# untitled.net
KiCad netlist of a schematic drawn in EAGLE
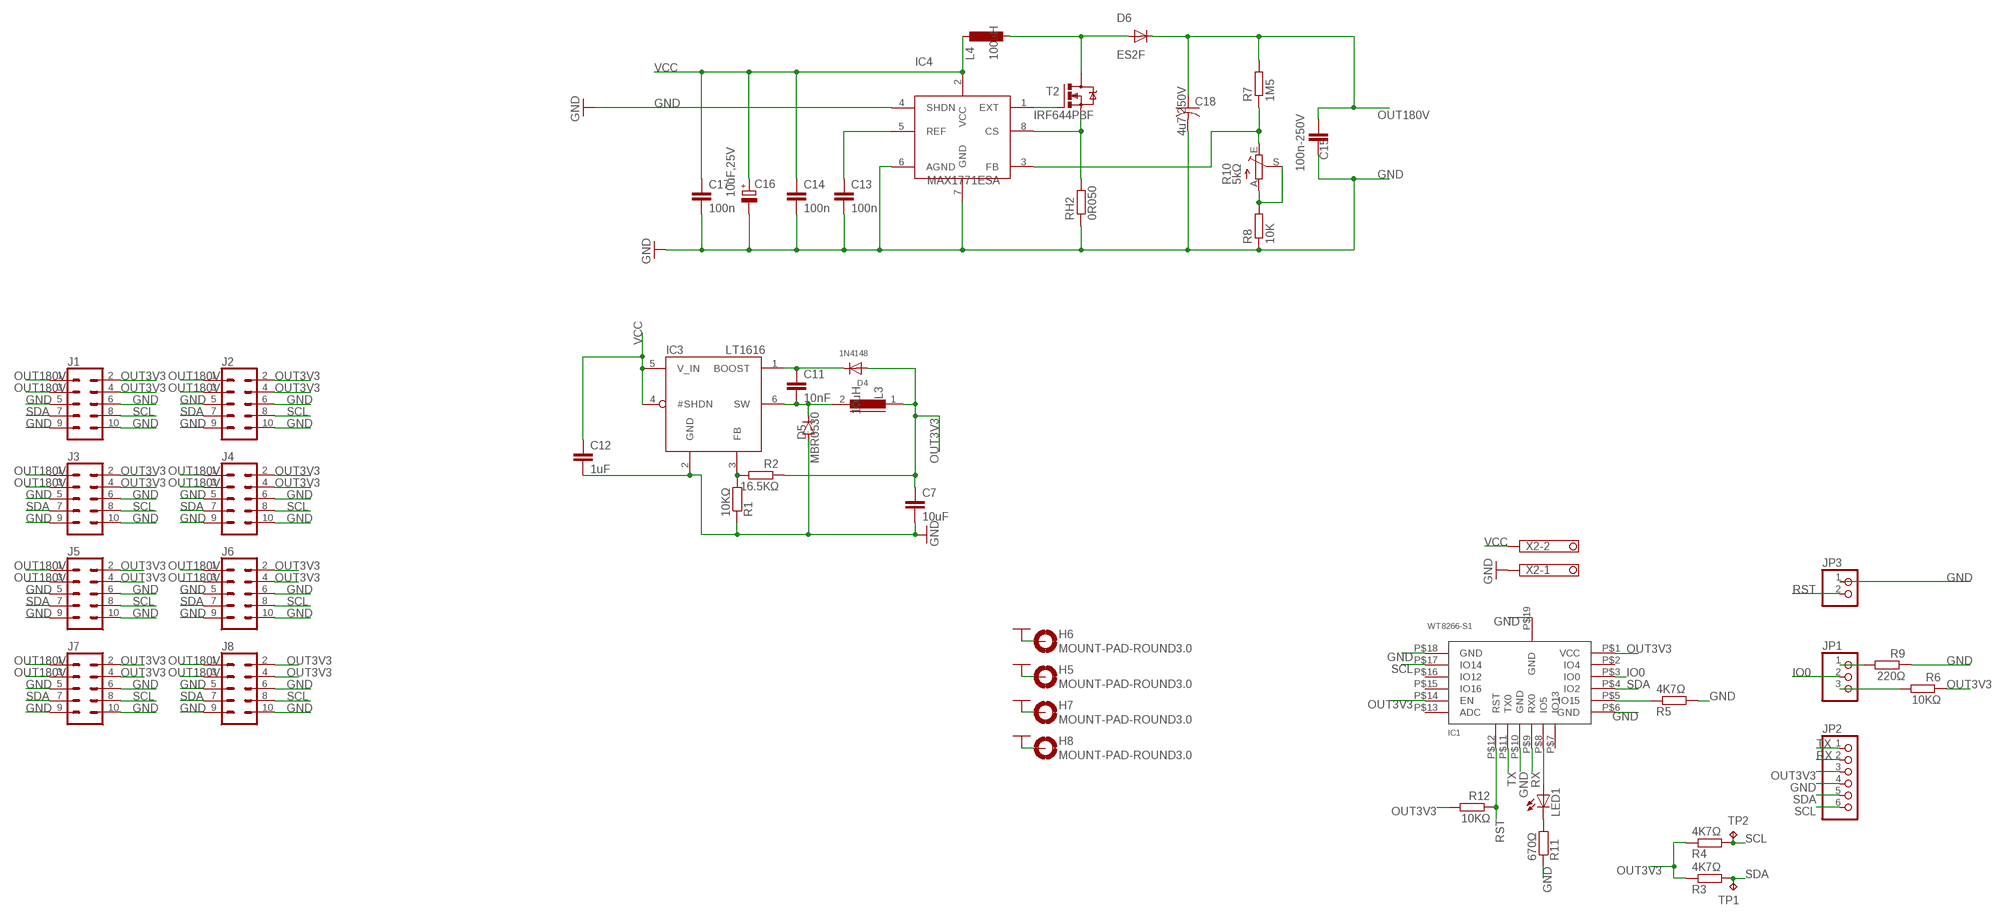
[diagram p0: schematic, sheet 1]

(export (version "E")
  (design (tool "Eeschema 10.0.6"))
  (components
    (comp (ref "C7")
      (value "10uF")
      (footprint "eagle-import:C1206")
      (libsource (lib "eagle-import") (part "C-EUC1206"))
    )
    (comp (ref "C11")
      (value "10nF")
      (footprint "eagle-import:C1206")
      (libsource (lib "eagle-import") (part "C-EUC1206"))
    )
    (comp (ref "C12")
      (value "1uF")
      (footprint "eagle-import:C1206")
      (libsource (lib "eagle-import") (part "C-EUC1206"))
    )
    (comp (ref "C13")
      (value "100n")
      (footprint "eagle-import:C1206")
      (libsource (lib "eagle-import") (part "C-EUC1206"))
    )
    (comp (ref "C14")
      (value "100n")
      (footprint "eagle-import:C1206")
      (libsource (lib "eagle-import") (part "C-EUC1206"))
    )
    (comp (ref "C15")
      (value "100n-250V")
      (footprint "eagle-import:C2420")
      (libsource (lib "eagle-import") (part "C-EU-2420"))
    )
    (comp (ref "C16")
      (value "10uF,25V")
      (footprint "eagle-import:C-EIA-7343")
      (libsource (lib "eagle-import") (part "C-POL-EU7343"))
    )
    (comp (ref "C17")
      (value "100n")
      (footprint "eagle-import:C1206")
      (libsource (lib "eagle-import") (part "C-EUC1206"))
    )
    (comp (ref "C18")
      (value "4u7 250V")
      (footprint "eagle-import:CAP_RADIAL_5MM")
      (fields
        (field (name "DIGIKEY_PART_NUMBER") "P5156-ND")
        (field (name "MANUFACTURER") "Panasonic Electronic Components")
        (field (name "MPN") "ECA-1EM102")
        (field (name "CREATED_BY") "PCBLayout.com")
      )
      (libsource (lib "eagle-import") (part "ECA-1EM102"))
    )
    (comp (ref "D4")
      (value "1N4148")
      (footprint "eagle-import:DO-1N4148")
      (libsource (lib "eagle-import") (part "DIODEDO-1N4148"))
    )
    (comp (ref "D5")
      (value "MBR0530")
      (footprint "eagle-import:SOD123")
      (libsource (lib "eagle-import") (part "diode_210_DIODE-SOD123"))
    )
    (comp (ref "D6")
      (value "ES2F")
      (footprint "eagle-import:SMC")
      (libsource (lib "eagle-import") (part "DIODE-SMC"))
    )
    (comp (ref "H5")
      (value "MOUNT-PAD-ROUND3.0")
      (footprint "eagle-import:3,0-PAD")
      (libsource (lib "eagle-import") (part "MOUNT-PAD-ROUND3.0"))
    )
    (comp (ref "H6")
      (value "MOUNT-PAD-ROUND3.0")
      (footprint "eagle-import:3,0-PAD")
      (libsource (lib "eagle-import") (part "MOUNT-PAD-ROUND3.0"))
    )
    (comp (ref "H7")
      (value "MOUNT-PAD-ROUND3.0")
      (footprint "eagle-import:3,0-PAD")
      (libsource (lib "eagle-import") (part "MOUNT-PAD-ROUND3.0"))
    )
    (comp (ref "H8")
      (value "MOUNT-PAD-ROUND3.0")
      (footprint "eagle-import:3,0-PAD")
      (libsource (lib "eagle-import") (part "MOUNT-PAD-ROUND3.0"))
    )
    (comp (ref "IC1")
      (value "WT8266-S1")
      (footprint "eagle-import:WT8266-S1")
      (libsource (lib "eagle-import") (part "WT8266-S1"))
    )
    (comp (ref "IC3")
      (value "LT1616")
      (footprint "eagle-import:SOT23-6")
      (libsource (lib "eagle-import") (part "LT1616"))
    )
    (comp (ref "IC4")
      (value "MAX1771ESA")
      (footprint "eagle-import:SO-8")
      (libsource (lib "eagle-import") (part "MAX1771ESA"))
    )
    (comp (ref "J1")
      (value "CONN_05X2PTH")
      (footprint "eagle-import:2X5")
      (libsource (lib "eagle-import") (part "CONN_05X2PTH"))
    )
    (comp (ref "J2")
      (value "CONN_05X2PTH")
      (footprint "eagle-import:2X5")
      (libsource (lib "eagle-import") (part "CONN_05X2PTH"))
    )
    (comp (ref "J3")
      (value "CONN_05X2PTH")
      (footprint "eagle-import:2X5")
      (libsource (lib "eagle-import") (part "CONN_05X2PTH"))
    )
    (comp (ref "J4")
      (value "CONN_05X2PTH")
      (footprint "eagle-import:2X5")
      (libsource (lib "eagle-import") (part "CONN_05X2PTH"))
    )
    (comp (ref "J5")
      (value "CONN_05X2PTH")
      (footprint "eagle-import:2X5")
      (libsource (lib "eagle-import") (part "CONN_05X2PTH"))
    )
    (comp (ref "J6")
      (value "CONN_05X2PTH")
      (footprint "eagle-import:2X5")
      (libsource (lib "eagle-import") (part "CONN_05X2PTH"))
    )
    (comp (ref "J7")
      (value "CONN_05X2PTH")
      (footprint "eagle-import:2X5")
      (libsource (lib "eagle-import") (part "CONN_05X2PTH"))
    )
    (comp (ref "J8")
      (value "CONN_05X2PTH")
      (footprint "eagle-import:2X5")
      (libsource (lib "eagle-import") (part "CONN_05X2PTH"))
    )
    (comp (ref "JP1")
      (value "PINHD-1X3")
      (footprint "eagle-import:1X03")
      (libsource (lib "eagle-import") (part "PINHD-1X3"))
    )
    (comp (ref "JP2")
      (value "PINHD-1X6")
      (footprint "eagle-import:1X06")
      (libsource (lib "eagle-import") (part "PINHD-1X6"))
    )
    (comp (ref "JP3")
      (value "PINHD-1X2")
      (footprint "eagle-import:1X02")
      (libsource (lib "eagle-import") (part "PINHD-1X2"))
    )
    (comp (ref "L3")
      (value "10uH")
      (footprint "eagle-import:82114R")
      (libsource (lib "eagle-import") (part "82114R"))
    )
    (comp (ref "L4")
      (value "100uH")
      (footprint "eagle-import:TJ3-U1")
      (libsource (lib "eagle-import") (part "L-EUTJ3-U1"))
    )
    (comp (ref "LED1")
      (value "LED3MM")
      (footprint "eagle-import:LED3MM")
      (libsource (lib "eagle-import") (part "LED3MM"))
    )
    (comp (ref "R1")
      (value "10KΩ")
      (footprint "eagle-import:R1206")
      (libsource (lib "eagle-import") (part "resistor_348_R-EU_R1206"))
    )
    (comp (ref "R2")
      (value "16.5KΩ")
      (footprint "eagle-import:R0805")
      (libsource (lib "eagle-import") (part "resistor_348_R-EU_R0805"))
    )
    (comp (ref "R3")
      (value "4K7Ω")
      (footprint "eagle-import:R1206")
      (libsource (lib "eagle-import") (part "resistor_348_R-EU_R1206"))
    )
    (comp (ref "R4")
      (value "4K7Ω")
      (footprint "eagle-import:R1206")
      (libsource (lib "eagle-import") (part "resistor_348_R-EU_R1206"))
    )
    (comp (ref "R5")
      (value "4K7Ω")
      (footprint "eagle-import:R1206")
      (libsource (lib "eagle-import") (part "resistor_348_R-EU_R1206"))
    )
    (comp (ref "R6")
      (value "10KΩ")
      (footprint "eagle-import:R1206")
      (libsource (lib "eagle-import") (part "resistor_348_R-EU_R1206"))
    )
    (comp (ref "R7")
      (value "1M5")
      (footprint "eagle-import:R2512")
      (libsource (lib "eagle-import") (part "R-EU_R2512"))
    )
    (comp (ref "R8")
      (value "10K")
      (footprint "eagle-import:R1206")
      (libsource (lib "eagle-import") (part "rcl_334_R-EU_R1206"))
    )
    (comp (ref "R9")
      (value "220Ω")
      (footprint "eagle-import:R1206")
      (libsource (lib "eagle-import") (part "resistor_348_R-EU_R1206"))
    )
    (comp (ref "R10")
      (value "5kΩ")
      (footprint "eagle-import:RS3")
      (libsource (lib "eagle-import") (part "TRIM_EU-RS3"))
    )
    (comp (ref "R11")
      (value "670Ω")
      (footprint "eagle-import:R1206")
      (libsource (lib "eagle-import") (part "resistor_348_R-EU_R1206"))
    )
    (comp (ref "R12")
      (value "10KΩ")
      (footprint "eagle-import:R1206")
      (libsource (lib "eagle-import") (part "resistor_348_R-EU_R1206"))
    )
    (comp (ref "RH2")
      (value "0R050")
      (footprint "eagle-import:R2512")
      (libsource (lib "eagle-import") (part "resistor_348_R-EU_R2512"))
    )
    (comp (ref "T2")
      (value "IRF644PBF")
      (footprint "eagle-import:TO220BV")
      (libsource (lib "eagle-import") (part "IRF740"))
    )
    (comp (ref "TP1")
      (value "TPTP18R")
      (footprint "eagle-import:TP18R")
      (libsource (lib "eagle-import") (part "TPTP18R"))
    )
    (comp (ref "TP2")
      (value "TPTP18R")
      (footprint "eagle-import:TP18R")
      (libsource (lib "eagle-import") (part "TPTP18R"))
    )
    (comp (ref "X2")
      (value "TERMINAL-BLOCK-3.5MM-2-PIN-LONG-PAD")
      (footprint "eagle-import:TERMINAL-BLOCK-2-PIN-3.5MM-LONG-PAD")
      (libsource (lib "eagle-import") (part "TERMINAL-BLOCK-3.5MM-2-PIN-LONG-PAD"))
    )
  )
  (nets
    (net (code "1") (name "/IO0") (class "Default")
      (node (ref "IC1") (pin "P$3") (pinfunction "IO0_P$3") (pintype "bidirectional"))
      (node (ref "JP1") (pin "2") (pinfunction "2_2") (pintype "passive"))
    )
    (net (code "2") (name "/OUT3V3") (class "Default")
      (node (ref "C7") (pin "1") (pinfunction "1_1") (pintype "passive"))
      (node (ref "D4") (pin "A") (pinfunction "A_A") (pintype "passive"))
      (node (ref "IC1") (pin "P$1") (pinfunction "VCC_P$1") (pintype "power_in"))
      (node (ref "IC1") (pin "P$14") (pinfunction "EN_P$14") (pintype "bidirectional"))
      (node (ref "J1") (pin "2") (pinfunction "2_2") (pintype "passive"))
      (node (ref "J1") (pin "4") (pinfunction "4_4") (pintype "passive"))
      (node (ref "J2") (pin "2") (pinfunction "2_2") (pintype "passive"))
      (node (ref "J2") (pin "4") (pinfunction "4_4") (pintype "passive"))
      (node (ref "J3") (pin "2") (pinfunction "2_2") (pintype "passive"))
      (node (ref "J3") (pin "4") (pinfunction "4_4") (pintype "passive"))
      (node (ref "J4") (pin "2") (pinfunction "2_2") (pintype "passive"))
      (node (ref "J4") (pin "4") (pinfunction "4_4") (pintype "passive"))
      (node (ref "J5") (pin "2") (pinfunction "2_2") (pintype "passive"))
      (node (ref "J5") (pin "4") (pinfunction "4_4") (pintype "passive"))
      (node (ref "J6") (pin "2") (pinfunction "2_2") (pintype "passive"))
      (node (ref "J6") (pin "4") (pinfunction "4_4") (pintype "passive"))
      (node (ref "J7") (pin "2") (pinfunction "2_2") (pintype "passive"))
      (node (ref "J7") (pin "4") (pinfunction "4_4") (pintype "passive"))
      (node (ref "J8") (pin "2") (pinfunction "2_2") (pintype "passive"))
      (node (ref "J8") (pin "4") (pinfunction "4_4") (pintype "passive"))
      (node (ref "JP2") (pin "3") (pinfunction "3_3") (pintype "passive"))
      (node (ref "L3") (pin "1") (pinfunction "1_1") (pintype "passive"))
      (node (ref "R12") (pin "2") (pinfunction "2_2") (pintype "passive"))
      (node (ref "R2") (pin "1") (pinfunction "1_1") (pintype "passive"))
      (node (ref "R3") (pin "1") (pinfunction "1_1") (pintype "passive"))
      (node (ref "R4") (pin "1") (pinfunction "1_1") (pintype "passive"))
      (node (ref "R6") (pin "1") (pinfunction "1_1") (pintype "passive"))
    )
    (net (code "3") (name "/OUT180V") (class "Default")
      (node (ref "C15") (pin "P$1") (pinfunction "1_P$1") (pintype "passive"))
      (node (ref "C18") (pin "1") (pinfunction "1_1") (pintype "passive"))
      (node (ref "D6") (pin "C") (pinfunction "C_C") (pintype "passive"))
      (node (ref "J1") (pin "1") (pinfunction "1_1") (pintype "passive"))
      (node (ref "J1") (pin "3") (pinfunction "3_3") (pintype "passive"))
      (node (ref "J2") (pin "1") (pinfunction "1_1") (pintype "passive"))
      (node (ref "J2") (pin "3") (pinfunction "3_3") (pintype "passive"))
      (node (ref "J3") (pin "1") (pinfunction "1_1") (pintype "passive"))
      (node (ref "J3") (pin "3") (pinfunction "3_3") (pintype "passive"))
      (node (ref "J4") (pin "1") (pinfunction "1_1") (pintype "passive"))
      (node (ref "J4") (pin "3") (pinfunction "3_3") (pintype "passive"))
      (node (ref "J5") (pin "1") (pinfunction "1_1") (pintype "passive"))
      (node (ref "J5") (pin "3") (pinfunction "3_3") (pintype "passive"))
      (node (ref "J6") (pin "1") (pinfunction "1_1") (pintype "passive"))
      (node (ref "J6") (pin "3") (pinfunction "3_3") (pintype "passive"))
      (node (ref "J7") (pin "1") (pinfunction "1_1") (pintype "passive"))
      (node (ref "J7") (pin "3") (pinfunction "3_3") (pintype "passive"))
      (node (ref "J8") (pin "1") (pinfunction "1_1") (pintype "passive"))
      (node (ref "J8") (pin "3") (pinfunction "3_3") (pintype "passive"))
      (node (ref "R7") (pin "2") (pinfunction "2_2") (pintype "passive"))
    )
    (net (code "4") (name "/RST") (class "Default")
      (node (ref "IC1") (pin "P$12") (pinfunction "RST_P$12") (pintype "bidirectional"))
      (node (ref "JP3") (pin "2") (pinfunction "2_2") (pintype "passive"))
      (node (ref "R12") (pin "1") (pinfunction "1_1") (pintype "passive"))
    )
    (net (code "5") (name "/RX") (class "Default")
      (node (ref "IC1") (pin "P$9") (pinfunction "RX0_P$9") (pintype "bidirectional"))
      (node (ref "JP2") (pin "2") (pinfunction "2_2") (pintype "passive"))
    )
    (net (code "6") (name "/SCL") (class "Default")
      (node (ref "IC1") (pin "P$17") (pinfunction "IO14_P$17") (pintype "bidirectional"))
      (node (ref "J1") (pin "8") (pinfunction "8_8") (pintype "passive"))
      (node (ref "J2") (pin "8") (pinfunction "8_8") (pintype "passive"))
      (node (ref "J3") (pin "8") (pinfunction "8_8") (pintype "passive"))
      (node (ref "J4") (pin "8") (pinfunction "8_8") (pintype "passive"))
      (node (ref "J5") (pin "8") (pinfunction "8_8") (pintype "passive"))
      (node (ref "J6") (pin "8") (pinfunction "8_8") (pintype "passive"))
      (node (ref "J7") (pin "8") (pinfunction "8_8") (pintype "passive"))
      (node (ref "J8") (pin "8") (pinfunction "8_8") (pintype "passive"))
      (node (ref "JP2") (pin "6") (pinfunction "6_6") (pintype "passive"))
      (node (ref "R4") (pin "2") (pinfunction "2_2") (pintype "passive"))
      (node (ref "TP2") (pin "TP") (pinfunction "TP_TP") (pintype "input"))
    )
    (net (code "7") (name "/SDA") (class "Default")
      (node (ref "IC1") (pin "P$4") (pinfunction "IO2_P$4") (pintype "bidirectional"))
      (node (ref "J1") (pin "7") (pinfunction "7_7") (pintype "passive"))
      (node (ref "J2") (pin "7") (pinfunction "7_7") (pintype "passive"))
      (node (ref "J3") (pin "7") (pinfunction "7_7") (pintype "passive"))
      (node (ref "J4") (pin "7") (pinfunction "7_7") (pintype "passive"))
      (node (ref "J5") (pin "7") (pinfunction "7_7") (pintype "passive"))
      (node (ref "J6") (pin "7") (pinfunction "7_7") (pintype "passive"))
      (node (ref "J7") (pin "7") (pinfunction "7_7") (pintype "passive"))
      (node (ref "J8") (pin "7") (pinfunction "7_7") (pintype "passive"))
      (node (ref "JP2") (pin "5") (pinfunction "5_5") (pintype "passive"))
      (node (ref "R3") (pin "2") (pinfunction "2_2") (pintype "passive"))
      (node (ref "TP1") (pin "TP") (pinfunction "TP_TP") (pintype "input"))
    )
    (net (code "8") (name "/TX") (class "Default")
      (node (ref "IC1") (pin "P$11") (pinfunction "TX0_P$11") (pintype "bidirectional"))
      (node (ref "JP2") (pin "1") (pinfunction "1_1") (pintype "passive"))
    )
    (net (code "9") (name "/VCC") (class "Default")
      (node (ref "C12") (pin "1") (pinfunction "1_1") (pintype "passive"))
      (node (ref "C14") (pin "1") (pinfunction "1_1") (pintype "passive"))
      (node (ref "C16") (pin "+") (pinfunction "+_+") (pintype "passive"))
      (node (ref "C17") (pin "1") (pinfunction "1_1") (pintype "passive"))
      (node (ref "IC3") (pin "4") (pinfunction "#SHDN_4") (pintype "passive"))
      (node (ref "IC3") (pin "5") (pinfunction "V_IN_5") (pintype "passive"))
      (node (ref "IC4") (pin "2") (pinfunction "VCC_2") (pintype "input"))
      (node (ref "L4") (pin "1") (pinfunction "1_1") (pintype "passive"))
      (node (ref "X2") (pin "2") (pinfunction "K_2") (pintype "passive"))
    )
    (net (code "10") (name "GND") (class "Default")
      (node (ref "C12") (pin "2") (pinfunction "2_2") (pintype "passive"))
      (node (ref "C13") (pin "2") (pinfunction "2_2") (pintype "passive"))
      (node (ref "C14") (pin "2") (pinfunction "2_2") (pintype "passive"))
      (node (ref "C15") (pin "P$2") (pinfunction "2_P$2") (pintype "passive"))
      (node (ref "C16") (pin "-") (pinfunction "-_-") (pintype "passive"))
      (node (ref "C17") (pin "2") (pinfunction "2_2") (pintype "passive"))
      (node (ref "C18") (pin "2") (pinfunction "2_2") (pintype "passive"))
      (node (ref "C7") (pin "2") (pinfunction "2_2") (pintype "passive"))
      (node (ref "D5") (pin "A") (pinfunction "A_A") (pintype "passive"))
      (node (ref "H5") (pin "B3,0") (pinfunction "MOUNT_B3,0") (pintype "passive"))
      (node (ref "H6") (pin "B3,0") (pinfunction "MOUNT_B3,0") (pintype "passive"))
      (node (ref "H7") (pin "B3,0") (pinfunction "MOUNT_B3,0") (pintype "passive"))
      (node (ref "H8") (pin "B3,0") (pinfunction "MOUNT_B3,0") (pintype "passive"))
      (node (ref "IC1") (pin "P$10") (pinfunction "GND_P$10") (pintype "power_in"))
      (node (ref "IC1") (pin "P$18") (pinfunction "GND_P$18") (pintype "power_in"))
      (node (ref "IC1") (pin "P$19") (pinfunction "GND_P$19") (pintype "power_in"))
      (node (ref "IC1") (pin "P$6") (pinfunction "GND_P$6") (pintype "power_in"))
      (node (ref "IC3") (pin "2") (pinfunction "GND_2") (pintype "power_in"))
      (node (ref "IC4") (pin "4") (pinfunction "SHDN_4") (pintype "input"))
      (node (ref "IC4") (pin "6") (pinfunction "AGND_6") (pintype "input"))
      (node (ref "IC4") (pin "7") (pinfunction "GND_7") (pintype "input"))
      (node (ref "J1") (pin "10") (pinfunction "10_10") (pintype "passive"))
      (node (ref "J1") (pin "5") (pinfunction "5_5") (pintype "passive"))
      (node (ref "J1") (pin "6") (pinfunction "6_6") (pintype "passive"))
      (node (ref "J1") (pin "9") (pinfunction "9_9") (pintype "passive"))
      (node (ref "J2") (pin "10") (pinfunction "10_10") (pintype "passive"))
      (node (ref "J2") (pin "5") (pinfunction "5_5") (pintype "passive"))
      (node (ref "J2") (pin "6") (pinfunction "6_6") (pintype "passive"))
      (node (ref "J2") (pin "9") (pinfunction "9_9") (pintype "passive"))
      (node (ref "J3") (pin "10") (pinfunction "10_10") (pintype "passive"))
      (node (ref "J3") (pin "5") (pinfunction "5_5") (pintype "passive"))
      (node (ref "J3") (pin "6") (pinfunction "6_6") (pintype "passive"))
      (node (ref "J3") (pin "9") (pinfunction "9_9") (pintype "passive"))
      (node (ref "J4") (pin "10") (pinfunction "10_10") (pintype "passive"))
      (node (ref "J4") (pin "5") (pinfunction "5_5") (pintype "passive"))
      (node (ref "J4") (pin "6") (pinfunction "6_6") (pintype "passive"))
      (node (ref "J4") (pin "9") (pinfunction "9_9") (pintype "passive"))
      (node (ref "J5") (pin "10") (pinfunction "10_10") (pintype "passive"))
      (node (ref "J5") (pin "5") (pinfunction "5_5") (pintype "passive"))
      (node (ref "J5") (pin "6") (pinfunction "6_6") (pintype "passive"))
      (node (ref "J5") (pin "9") (pinfunction "9_9") (pintype "passive"))
      (node (ref "J6") (pin "10") (pinfunction "10_10") (pintype "passive"))
      (node (ref "J6") (pin "5") (pinfunction "5_5") (pintype "passive"))
      (node (ref "J6") (pin "6") (pinfunction "6_6") (pintype "passive"))
      (node (ref "J6") (pin "9") (pinfunction "9_9") (pintype "passive"))
      (node (ref "J7") (pin "10") (pinfunction "10_10") (pintype "passive"))
      (node (ref "J7") (pin "5") (pinfunction "5_5") (pintype "passive"))
      (node (ref "J7") (pin "6") (pinfunction "6_6") (pintype "passive"))
      (node (ref "J7") (pin "9") (pinfunction "9_9") (pintype "passive"))
      (node (ref "J8") (pin "10") (pinfunction "10_10") (pintype "passive"))
      (node (ref "J8") (pin "5") (pinfunction "5_5") (pintype "passive"))
      (node (ref "J8") (pin "6") (pinfunction "6_6") (pintype "passive"))
      (node (ref "J8") (pin "9") (pinfunction "9_9") (pintype "passive"))
      (node (ref "JP2") (pin "4") (pinfunction "4_4") (pintype "passive"))
      (node (ref "JP3") (pin "1") (pinfunction "1_1") (pintype "passive"))
      (node (ref "R1") (pin "1") (pinfunction "1_1") (pintype "passive"))
      (node (ref "R11") (pin "1") (pinfunction "1_1") (pintype "passive"))
      (node (ref "R5") (pin "2") (pinfunction "2_2") (pintype "passive"))
      (node (ref "R8") (pin "1") (pinfunction "1_1") (pintype "passive"))
      (node (ref "R9") (pin "1") (pinfunction "1_1") (pintype "passive"))
      (node (ref "RH2") (pin "1") (pinfunction "1_1") (pintype "passive"))
      (node (ref "X2") (pin "1") (pinfunction "K_1") (pintype "passive"))
    )
    (net (code "11") (name "Net-(D6-PadA)") (class "Default")
      (node (ref "D6") (pin "A") (pinfunction "A_A") (pintype "passive"))
      (node (ref "L4") (pin "2") (pinfunction "2_2") (pintype "passive"))
      (node (ref "T2") (pin "D") (pinfunction "D_D") (pintype "passive"))
    )
    (net (code "12") (name "Net-(IC1-IO5)") (class "Default")
      (node (ref "IC1") (pin "P$8") (pinfunction "IO5_P$8") (pintype "bidirectional"))
      (node (ref "LED1") (pin "A") (pinfunction "A_A") (pintype "passive"))
    )
    (net (code "13") (name "Net-(IC1-IO15)") (class "Default")
      (node (ref "IC1") (pin "P$5") (pinfunction "IO15_P$5") (pintype "bidirectional"))
      (node (ref "R5") (pin "1") (pinfunction "1_1") (pintype "passive"))
    )
    (net (code "14") (name "Net-(IC3-BOOST)") (class "Default")
      (node (ref "C11") (pin "1") (pinfunction "1_1") (pintype "passive"))
      (node (ref "D4") (pin "C") (pinfunction "C_C") (pintype "passive"))
      (node (ref "IC3") (pin "1") (pinfunction "BOOST_1") (pintype "passive"))
    )
    (net (code "15") (name "Net-(IC3-FB)") (class "Default")
      (node (ref "IC3") (pin "3") (pinfunction "FB_3") (pintype "passive"))
      (node (ref "R1") (pin "2") (pinfunction "2_2") (pintype "passive"))
      (node (ref "R2") (pin "2") (pinfunction "2_2") (pintype "passive"))
    )
    (net (code "16") (name "Net-(IC3-SW)") (class "Default")
      (node (ref "C11") (pin "2") (pinfunction "2_2") (pintype "passive"))
      (node (ref "D5") (pin "C") (pinfunction "C_C") (pintype "passive"))
      (node (ref "IC3") (pin "6") (pinfunction "SW_6") (pintype "passive"))
      (node (ref "L3") (pin "2") (pinfunction "2_2") (pintype "passive"))
    )
    (net (code "17") (name "Net-(IC4-CS)") (class "Default")
      (node (ref "IC4") (pin "8") (pinfunction "CS_8") (pintype "input"))
      (node (ref "RH2") (pin "2") (pinfunction "2_2") (pintype "passive"))
      (node (ref "T2") (pin "S") (pinfunction "S_S") (pintype "passive"))
    )
    (net (code "18") (name "Net-(IC4-EXT)") (class "Default")
      (node (ref "IC4") (pin "1") (pinfunction "EXT_1") (pintype "output"))
      (node (ref "T2") (pin "G") (pinfunction "G_G") (pintype "passive"))
    )
    (net (code "19") (name "Net-(IC4-FB)") (class "Default")
      (node (ref "IC4") (pin "3") (pinfunction "FB_3") (pintype "input"))
      (node (ref "R10") (pin "E") (pinfunction "E_E") (pintype "passive"))
      (node (ref "R7") (pin "1") (pinfunction "1_1") (pintype "passive"))
    )
    (net (code "20") (name "Net-(IC4-REF)") (class "Default")
      (node (ref "C13") (pin "1") (pinfunction "1_1") (pintype "passive"))
      (node (ref "IC4") (pin "5") (pinfunction "REF_5") (pintype "input"))
    )
    (net (code "21") (name "Net-(JP1-Pad1)") (class "Default")
      (node (ref "JP1") (pin "1") (pinfunction "1_1") (pintype "passive"))
      (node (ref "R9") (pin "2") (pinfunction "2_2") (pintype "passive"))
    )
    (net (code "22") (name "Net-(JP1-Pad3)") (class "Default")
      (node (ref "JP1") (pin "3") (pinfunction "3_3") (pintype "passive"))
      (node (ref "R6") (pin "2") (pinfunction "2_2") (pintype "passive"))
    )
    (net (code "23") (name "Net-(LED1-C)") (class "Default")
      (node (ref "LED1") (pin "K") (pinfunction "C_K") (pintype "passive"))
      (node (ref "R11") (pin "2") (pinfunction "2_2") (pintype "passive"))
    )
    (net (code "24") (name "Net-(R10-PadA)") (class "Default")
      (node (ref "R10") (pin "A") (pinfunction "A_A") (pintype "passive"))
      (node (ref "R10") (pin "S") (pinfunction "S_S") (pintype "passive"))
      (node (ref "R8") (pin "2") (pinfunction "2_2") (pintype "passive"))
    )
    (net (code "25") (name "unconnected-(IC1-ADC-PadP$13)") (class "Default")
      (node (ref "IC1") (pin "P$13") (pinfunction "ADC_P$13") (pintype "bidirectional"))
    )
    (net (code "26") (name "unconnected-(IC1-IO4-PadP$2)") (class "Default")
      (node (ref "IC1") (pin "P$2") (pinfunction "IO4_P$2") (pintype "bidirectional"))
    )
    (net (code "27") (name "unconnected-(IC1-IO12-PadP$16)") (class "Default")
      (node (ref "IC1") (pin "P$16") (pinfunction "IO12_P$16") (pintype "bidirectional"))
    )
    (net (code "28") (name "unconnected-(IC1-IO13-PadP$7)") (class "Default")
      (node (ref "IC1") (pin "P$7") (pinfunction "IO13_P$7") (pintype "bidirectional"))
    )
    (net (code "29") (name "unconnected-(IC1-IO16-PadP$15)") (class "Default")
      (node (ref "IC1") (pin "P$15") (pinfunction "IO16_P$15") (pintype "bidirectional"))
    )
  )
)
